# PowerManagement_uC.net
KiCad netlist of a schematic drawn in Altium Designer
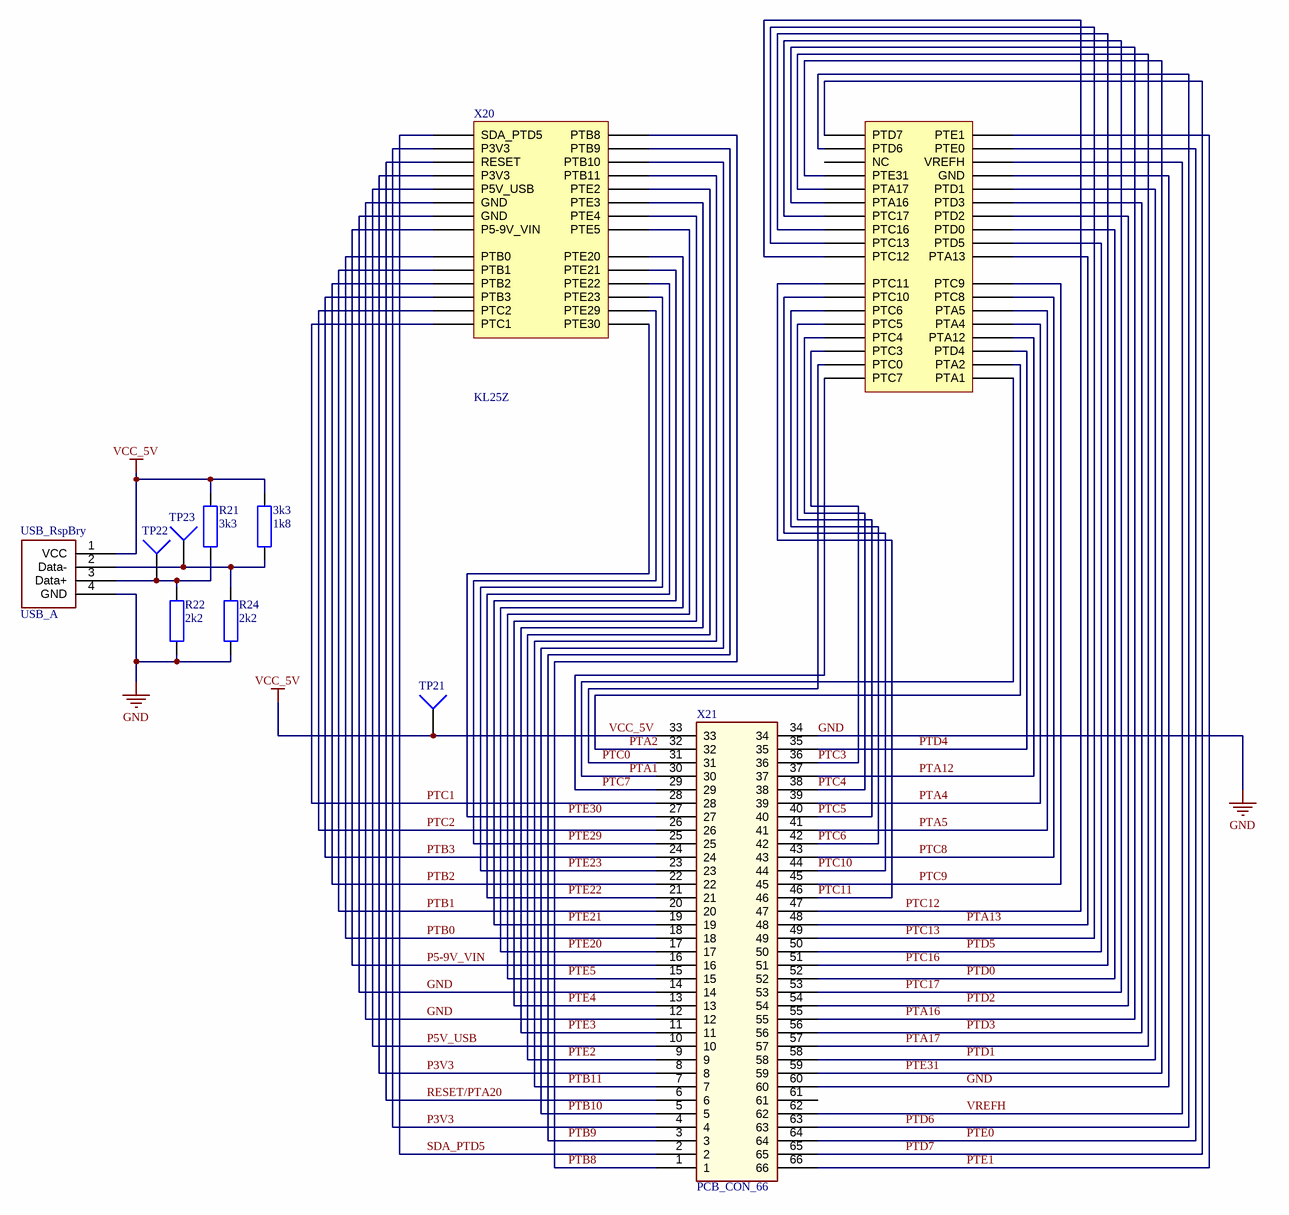
[diagram p0: PowerManagement_uC.SchDoc]

(export (version "E")
  (design (tool "Eeschema 10.0.6"))
  (components
    (comp (ref "3k3")
      (value "1k8")
      (footprint "0805")
      (description "Normaler Widerstand")
      (libsource (lib "SPICE_HSLU") (part "R?"))
    )
    (comp (ref "R21")
      (value "3k3")
      (footprint "0805")
      (description "Normaler Widerstand")
      (libsource (lib "SPICE_HSLU") (part "R?"))
    )
    (comp (ref "R22")
      (value "2k2")
      (footprint "0805")
      (description "Normaler Widerstand")
      (libsource (lib "SPICE_HSLU") (part "R?"))
    )
    (comp (ref "R24")
      (value "2k2")
      (footprint "0805")
      (description "Normaler Widerstand")
      (libsource (lib "SPICE_HSLU") (part "R?"))
    )
    (comp (ref "TP21")
      (value "~")
      (footprint "PIN1")
      (fields (field (name "PUBLISHER") "Altium Limited"))
      (libsource (lib "Miscellaneous Connectors") (part "Socket"))
    )
    (comp (ref "TP22")
      (value "~")
      (footprint "PIN1")
      (fields (field (name "PUBLISHER") "Altium Limited"))
      (libsource (lib "Miscellaneous Connectors") (part "Socket"))
    )
    (comp (ref "TP23")
      (value "~")
      (footprint "PIN1")
      (fields (field (name "PUBLISHER") "Altium Limited"))
      (libsource (lib "Miscellaneous Connectors") (part "Socket"))
    )
    (comp (ref "USB_RspBry") (value "USB_A") (footprint "USB_A") (libsource (lib "PREN2Lib") (part "USB_A")))
    (comp (ref "X20")
      (value "KL25Z")
      (footprint "Freedom KL25Z Headerarray")
      (description "FRDM KL25Z Shield")
      (libsource (lib "FreedomKL25Z") (part "Freedom KL25Z Header"))
    )
    (comp (ref "X21")
      (value "PCB_CON_66")
      (footprint "PCB_CON_66_PLUG")
      (description "Connects a PCB with another. This scheme is either jack or plug, depends on footprint")
      (libsource (lib "PREN2Lib") (part "PCB_CON_66"))
    )
  )
  (nets
    (net (code "1") (name "/P3V3") (class "Default")
      (node (ref "X20") (pin "3") (pinfunction "P3V3_3") (pintype "passive"))
      (node (ref "X20") (pin "7") (pinfunction "P3V3_7") (pintype "passive"))
      (node (ref "X21") (pin "4") (pinfunction "4_4") (pintype "passive"))
      (node (ref "X21") (pin "8") (pinfunction "8_8") (pintype "passive"))
    )
    (net (code "2") (name "/P5-9V_VIN") (class "Default")
      (node (ref "X20") (pin "15") (pinfunction "P5-9V_VIN_15") (pintype "passive"))
      (node (ref "X21") (pin "16") (pinfunction "16_16") (pintype "passive"))
    )
    (net (code "3") (name "/P5V_USB") (class "Default")
      (node (ref "X20") (pin "9") (pinfunction "P5V_USB_9") (pintype "passive"))
      (node (ref "X21") (pin "10") (pinfunction "10_10") (pintype "passive"))
    )
    (net (code "4") (name "/PTA1") (class "Default")
      (node (ref "X20") (pin "64") (pinfunction "PTA1_64") (pintype "passive"))
      (node (ref "X21") (pin "30") (pinfunction "30_30") (pintype "passive"))
    )
    (net (code "5") (name "/PTA2") (class "Default")
      (node (ref "X20") (pin "62") (pinfunction "PTA2_62") (pintype "passive"))
      (node (ref "X21") (pin "32") (pinfunction "32_32") (pintype "passive"))
    )
    (net (code "6") (name "/PTA4") (class "Default")
      (node (ref "X20") (pin "56") (pinfunction "PTA4_56") (pintype "passive"))
      (node (ref "X21") (pin "39") (pinfunction "39_39") (pintype "passive"))
    )
    (net (code "7") (name "/PTA5") (class "Default")
      (node (ref "X20") (pin "54") (pinfunction "PTA5_54") (pintype "passive"))
      (node (ref "X21") (pin "41") (pinfunction "41_41") (pintype "passive"))
    )
    (net (code "8") (name "/PTA12") (class "Default")
      (node (ref "X20") (pin "58") (pinfunction "PTA12_58") (pintype "passive"))
      (node (ref "X21") (pin "37") (pinfunction "37_37") (pintype "passive"))
    )
    (net (code "9") (name "/PTA13") (class "Default")
      (node (ref "X20") (pin "48") (pinfunction "PTA13_48") (pintype "passive"))
      (node (ref "X21") (pin "48") (pinfunction "48_48") (pintype "passive"))
    )
    (net (code "10") (name "/PTA16") (class "Default")
      (node (ref "X20") (pin "39") (pinfunction "PTA16_39") (pintype "passive"))
      (node (ref "X21") (pin "55") (pinfunction "55_55") (pintype "passive"))
    )
    (net (code "11") (name "/PTA17") (class "Default")
      (node (ref "X20") (pin "37") (pinfunction "PTA17_37") (pintype "passive"))
      (node (ref "X21") (pin "57") (pinfunction "57_57") (pintype "passive"))
    )
    (net (code "12") (name "/PTB0") (class "Default")
      (node (ref "X20") (pin "17") (pinfunction "PTB0_17") (pintype "passive"))
      (node (ref "X21") (pin "18") (pinfunction "18_18") (pintype "passive"))
    )
    (net (code "13") (name "/PTB1") (class "Default")
      (node (ref "X20") (pin "19") (pinfunction "PTB1_19") (pintype "passive"))
      (node (ref "X21") (pin "20") (pinfunction "20_20") (pintype "passive"))
    )
    (net (code "14") (name "/PTB2") (class "Default")
      (node (ref "X20") (pin "21") (pinfunction "PTB2_21") (pintype "passive"))
      (node (ref "X21") (pin "22") (pinfunction "22_22") (pintype "passive"))
    )
    (net (code "15") (name "/PTB3") (class "Default")
      (node (ref "X20") (pin "23") (pinfunction "PTB3_23") (pintype "passive"))
      (node (ref "X21") (pin "24") (pinfunction "24_24") (pintype "passive"))
    )
    (net (code "16") (name "/PTB8") (class "Default")
      (node (ref "X20") (pin "2") (pinfunction "PTB8_2") (pintype "passive"))
      (node (ref "X21") (pin "1") (pinfunction "1_1") (pintype "passive"))
    )
    (net (code "17") (name "/PTB9") (class "Default")
      (node (ref "X20") (pin "4") (pinfunction "PTB9_4") (pintype "passive"))
      (node (ref "X21") (pin "3") (pinfunction "3_3") (pintype "passive"))
    )
    (net (code "18") (name "/PTB10") (class "Default")
      (node (ref "X20") (pin "6") (pinfunction "PTB10_6") (pintype "passive"))
      (node (ref "X21") (pin "5") (pinfunction "5_5") (pintype "passive"))
    )
    (net (code "19") (name "/PTB11") (class "Default")
      (node (ref "X20") (pin "8") (pinfunction "PTB11_8") (pintype "passive"))
      (node (ref "X21") (pin "7") (pinfunction "7_7") (pintype "passive"))
    )
    (net (code "20") (name "/PTC0") (class "Default")
      (node (ref "X20") (pin "61") (pinfunction "PTC0_61") (pintype "passive"))
      (node (ref "X21") (pin "31") (pinfunction "31_31") (pintype "passive"))
    )
    (net (code "21") (name "/PTC1") (class "Default")
      (node (ref "X20") (pin "27") (pinfunction "PTC1_27") (pintype "passive"))
      (node (ref "X21") (pin "28") (pinfunction "28_28") (pintype "passive"))
    )
    (net (code "22") (name "/PTC2") (class "Default")
      (node (ref "X20") (pin "25") (pinfunction "PTC2_25") (pintype "passive"))
      (node (ref "X21") (pin "26") (pinfunction "26_26") (pintype "passive"))
    )
    (net (code "23") (name "/PTC3") (class "Default")
      (node (ref "X20") (pin "59") (pinfunction "PTC3_59") (pintype "passive"))
      (node (ref "X21") (pin "36") (pinfunction "36_36") (pintype "passive"))
    )
    (net (code "24") (name "/PTC4") (class "Default")
      (node (ref "X20") (pin "57") (pinfunction "PTC4_57") (pintype "passive"))
      (node (ref "X21") (pin "38") (pinfunction "38_38") (pintype "passive"))
    )
    (net (code "25") (name "/PTC5") (class "Default")
      (node (ref "X20") (pin "55") (pinfunction "PTC5_55") (pintype "passive"))
      (node (ref "X21") (pin "40") (pinfunction "40_40") (pintype "passive"))
    )
    (net (code "26") (name "/PTC6") (class "Default")
      (node (ref "X20") (pin "53") (pinfunction "PTC6_53") (pintype "passive"))
      (node (ref "X21") (pin "42") (pinfunction "42_42") (pintype "passive"))
    )
    (net (code "27") (name "/PTC7") (class "Default")
      (node (ref "X20") (pin "63") (pinfunction "PTC7_63") (pintype "passive"))
      (node (ref "X21") (pin "29") (pinfunction "29_29") (pintype "passive"))
    )
    (net (code "28") (name "/PTC8") (class "Default")
      (node (ref "X20") (pin "52") (pinfunction "PTC8_52") (pintype "passive"))
      (node (ref "X21") (pin "43") (pinfunction "43_43") (pintype "passive"))
    )
    (net (code "29") (name "/PTC9") (class "Default")
      (node (ref "X20") (pin "50") (pinfunction "PTC9_50") (pintype "passive"))
      (node (ref "X21") (pin "45") (pinfunction "45_45") (pintype "passive"))
    )
    (net (code "30") (name "/PTC10") (class "Default")
      (node (ref "X20") (pin "51") (pinfunction "PTC10_51") (pintype "passive"))
      (node (ref "X21") (pin "44") (pinfunction "44_44") (pintype "passive"))
    )
    (net (code "31") (name "/PTC11") (class "Default")
      (node (ref "X20") (pin "49") (pinfunction "PTC11_49") (pintype "passive"))
      (node (ref "X21") (pin "46") (pinfunction "46_46") (pintype "passive"))
    )
    (net (code "32") (name "/PTC12") (class "Default")
      (node (ref "X20") (pin "47") (pinfunction "PTC12_47") (pintype "passive"))
      (node (ref "X21") (pin "47") (pinfunction "47_47") (pintype "passive"))
    )
    (net (code "33") (name "/PTC13") (class "Default")
      (node (ref "X20") (pin "45") (pinfunction "PTC13_45") (pintype "passive"))
      (node (ref "X21") (pin "49") (pinfunction "49_49") (pintype "passive"))
    )
    (net (code "34") (name "/PTC16") (class "Default")
      (node (ref "X20") (pin "43") (pinfunction "PTC16_43") (pintype "passive"))
      (node (ref "X21") (pin "51") (pinfunction "51_51") (pintype "passive"))
    )
    (net (code "35") (name "/PTC17") (class "Default")
      (node (ref "X20") (pin "41") (pinfunction "PTC17_41") (pintype "passive"))
      (node (ref "X21") (pin "53") (pinfunction "53_53") (pintype "passive"))
    )
    (net (code "36") (name "/PTD0") (class "Default")
      (node (ref "X20") (pin "44") (pinfunction "PTD0_44") (pintype "passive"))
      (node (ref "X21") (pin "52") (pinfunction "52_52") (pintype "passive"))
    )
    (net (code "37") (name "/PTD1") (class "Default")
      (node (ref "X20") (pin "38") (pinfunction "PTD1_38") (pintype "passive"))
      (node (ref "X21") (pin "58") (pinfunction "58_58") (pintype "passive"))
    )
    (net (code "38") (name "/PTD2") (class "Default")
      (node (ref "X20") (pin "42") (pinfunction "PTD2_42") (pintype "passive"))
      (node (ref "X21") (pin "54") (pinfunction "54_54") (pintype "passive"))
    )
    (net (code "39") (name "/PTD3") (class "Default")
      (node (ref "X20") (pin "40") (pinfunction "PTD3_40") (pintype "passive"))
      (node (ref "X21") (pin "56") (pinfunction "56_56") (pintype "passive"))
    )
    (net (code "40") (name "/PTD4") (class "Default")
      (node (ref "X20") (pin "60") (pinfunction "PTD4_60") (pintype "passive"))
      (node (ref "X21") (pin "35") (pinfunction "35_35") (pintype "passive"))
    )
    (net (code "41") (name "/PTD5") (class "Default")
      (node (ref "X20") (pin "46") (pinfunction "PTD5_46") (pintype "passive"))
      (node (ref "X21") (pin "50") (pinfunction "50_50") (pintype "passive"))
    )
    (net (code "42") (name "/PTD6") (class "Default")
      (node (ref "X20") (pin "31") (pinfunction "PTD6_31") (pintype "passive"))
      (node (ref "X21") (pin "63") (pinfunction "63_63") (pintype "passive"))
    )
    (net (code "43") (name "/PTD7") (class "Default")
      (node (ref "X20") (pin "29") (pinfunction "PTD7_29") (pintype "passive"))
      (node (ref "X21") (pin "65") (pinfunction "65_65") (pintype "passive"))
    )
    (net (code "44") (name "/PTE0") (class "Default")
      (node (ref "X20") (pin "32") (pinfunction "PTE0_32") (pintype "passive"))
      (node (ref "X21") (pin "64") (pinfunction "64_64") (pintype "passive"))
    )
    (net (code "45") (name "/PTE1") (class "Default")
      (node (ref "X20") (pin "30") (pinfunction "PTE1_30") (pintype "passive"))
      (node (ref "X21") (pin "66") (pinfunction "66_66") (pintype "passive"))
    )
    (net (code "46") (name "/PTE2") (class "Default")
      (node (ref "X20") (pin "10") (pinfunction "PTE2_10") (pintype "passive"))
      (node (ref "X21") (pin "9") (pinfunction "9_9") (pintype "passive"))
    )
    (net (code "47") (name "/PTE3") (class "Default")
      (node (ref "X20") (pin "12") (pinfunction "PTE3_12") (pintype "passive"))
      (node (ref "X21") (pin "11") (pinfunction "11_11") (pintype "passive"))
    )
    (net (code "48") (name "/PTE4") (class "Default")
      (node (ref "X20") (pin "14") (pinfunction "PTE4_14") (pintype "passive"))
      (node (ref "X21") (pin "13") (pinfunction "13_13") (pintype "passive"))
    )
    (net (code "49") (name "/PTE5") (class "Default")
      (node (ref "X20") (pin "16") (pinfunction "PTE5_16") (pintype "passive"))
      (node (ref "X21") (pin "15") (pinfunction "15_15") (pintype "passive"))
    )
    (net (code "50") (name "/PTE20") (class "Default")
      (node (ref "X20") (pin "18") (pinfunction "PTE20_18") (pintype "passive"))
      (node (ref "X21") (pin "17") (pinfunction "17_17") (pintype "passive"))
    )
    (net (code "51") (name "/PTE21") (class "Default")
      (node (ref "X20") (pin "20") (pinfunction "PTE21_20") (pintype "passive"))
      (node (ref "X21") (pin "19") (pinfunction "19_19") (pintype "passive"))
    )
    (net (code "52") (name "/PTE22") (class "Default")
      (node (ref "X20") (pin "22") (pinfunction "PTE22_22") (pintype "passive"))
      (node (ref "X21") (pin "21") (pinfunction "21_21") (pintype "passive"))
    )
    (net (code "53") (name "/PTE23") (class "Default")
      (node (ref "X20") (pin "24") (pinfunction "PTE23_24") (pintype "passive"))
      (node (ref "X21") (pin "23") (pinfunction "23_23") (pintype "passive"))
    )
    (net (code "54") (name "/PTE29") (class "Default")
      (node (ref "X20") (pin "26") (pinfunction "PTE29_26") (pintype "passive"))
      (node (ref "X21") (pin "25") (pinfunction "25_25") (pintype "passive"))
    )
    (net (code "55") (name "/PTE30") (class "Default")
      (node (ref "X20") (pin "28") (pinfunction "PTE30_28") (pintype "passive"))
      (node (ref "X21") (pin "27") (pinfunction "27_27") (pintype "passive"))
    )
    (net (code "56") (name "/PTE31") (class "Default")
      (node (ref "X20") (pin "35") (pinfunction "PTE31_35") (pintype "passive"))
      (node (ref "X21") (pin "59") (pinfunction "59_59") (pintype "passive"))
    )
    (net (code "57") (name "/RESET{slash}PTA20") (class "Default")
      (node (ref "X20") (pin "5") (pinfunction "RESET_5") (pintype "passive"))
      (node (ref "X21") (pin "6") (pinfunction "6_6") (pintype "passive"))
    )
    (net (code "58") (name "/SDA_PTD5") (class "Default")
      (node (ref "X20") (pin "1") (pinfunction "SDA_PTD5_1") (pintype "passive"))
      (node (ref "X21") (pin "2") (pinfunction "2_2") (pintype "passive"))
    )
    (net (code "59") (name "/VREFH") (class "Default")
      (node (ref "X20") (pin "34") (pinfunction "VREFH_34") (pintype "passive"))
      (node (ref "X21") (pin "62") (pinfunction "62_62") (pintype "passive"))
    )
    (net (code "60") (name "GND") (class "Default")
      (node (ref "R22") (pin "1") (pintype "passive"))
      (node (ref "R24") (pin "1") (pintype "passive"))
      (node (ref "USB_RspBry") (pin "4") (pinfunction "GND_4") (pintype "passive"))
      (node (ref "X20") (pin "11") (pinfunction "GND_11") (pintype "passive"))
      (node (ref "X20") (pin "13") (pinfunction "GND_13") (pintype "passive"))
      (node (ref "X20") (pin "36") (pinfunction "GND_36") (pintype "passive"))
      (node (ref "X21") (pin "12") (pinfunction "12_12") (pintype "passive"))
      (node (ref "X21") (pin "14") (pinfunction "14_14") (pintype "passive"))
      (node (ref "X21") (pin "34") (pinfunction "34_34") (pintype "passive"))
      (node (ref "X21") (pin "60") (pinfunction "60_60") (pintype "passive"))
    )
    (net (code "61") (name "Net-(USB_RspBry-Data+)") (class "Default")
      (node (ref "R21") (pin "1") (pintype "passive"))
      (node (ref "R22") (pin "2") (pintype "passive"))
      (node (ref "TP22") (pin "1") (pinfunction "1_1") (pintype "passive"))
      (node (ref "USB_RspBry") (pin "3") (pinfunction "Data+_3") (pintype "passive"))
    )
    (net (code "62") (name "Net-(USB_RspBry-Data-)") (class "Default")
      (node (ref "3k3") (pin "1") (pintype "passive"))
      (node (ref "R24") (pin "2") (pintype "passive"))
      (node (ref "TP23") (pin "1") (pinfunction "1_1") (pintype "passive"))
      (node (ref "USB_RspBry") (pin "2") (pinfunction "Data-_2") (pintype "passive"))
    )
    (net (code "63") (name "VCC_5V") (class "Default")
      (node (ref "3k3") (pin "2") (pintype "passive"))
      (node (ref "R21") (pin "2") (pintype "passive"))
      (node (ref "TP21") (pin "1") (pinfunction "1_1") (pintype "passive"))
      (node (ref "USB_RspBry") (pin "1") (pinfunction "VCC_1") (pintype "passive"))
      (node (ref "X21") (pin "33") (pinfunction "33_33") (pintype "passive"))
    )
    (net (code "64") (name "unconnected-(X20-NC-Pad33)") (class "Default")
      (node (ref "X20") (pin "33") (pinfunction "NC_33") (pintype "passive"))
    )
    (net (code "65") (name "unconnected-(X21-Pad61)") (class "Default")
      (node (ref "X21") (pin "61") (pinfunction "61_61") (pintype "passive"))
    )
  )
)
